# PLACA_CONECTORES.net
KiCad netlist of a schematic drawn in EAGLE
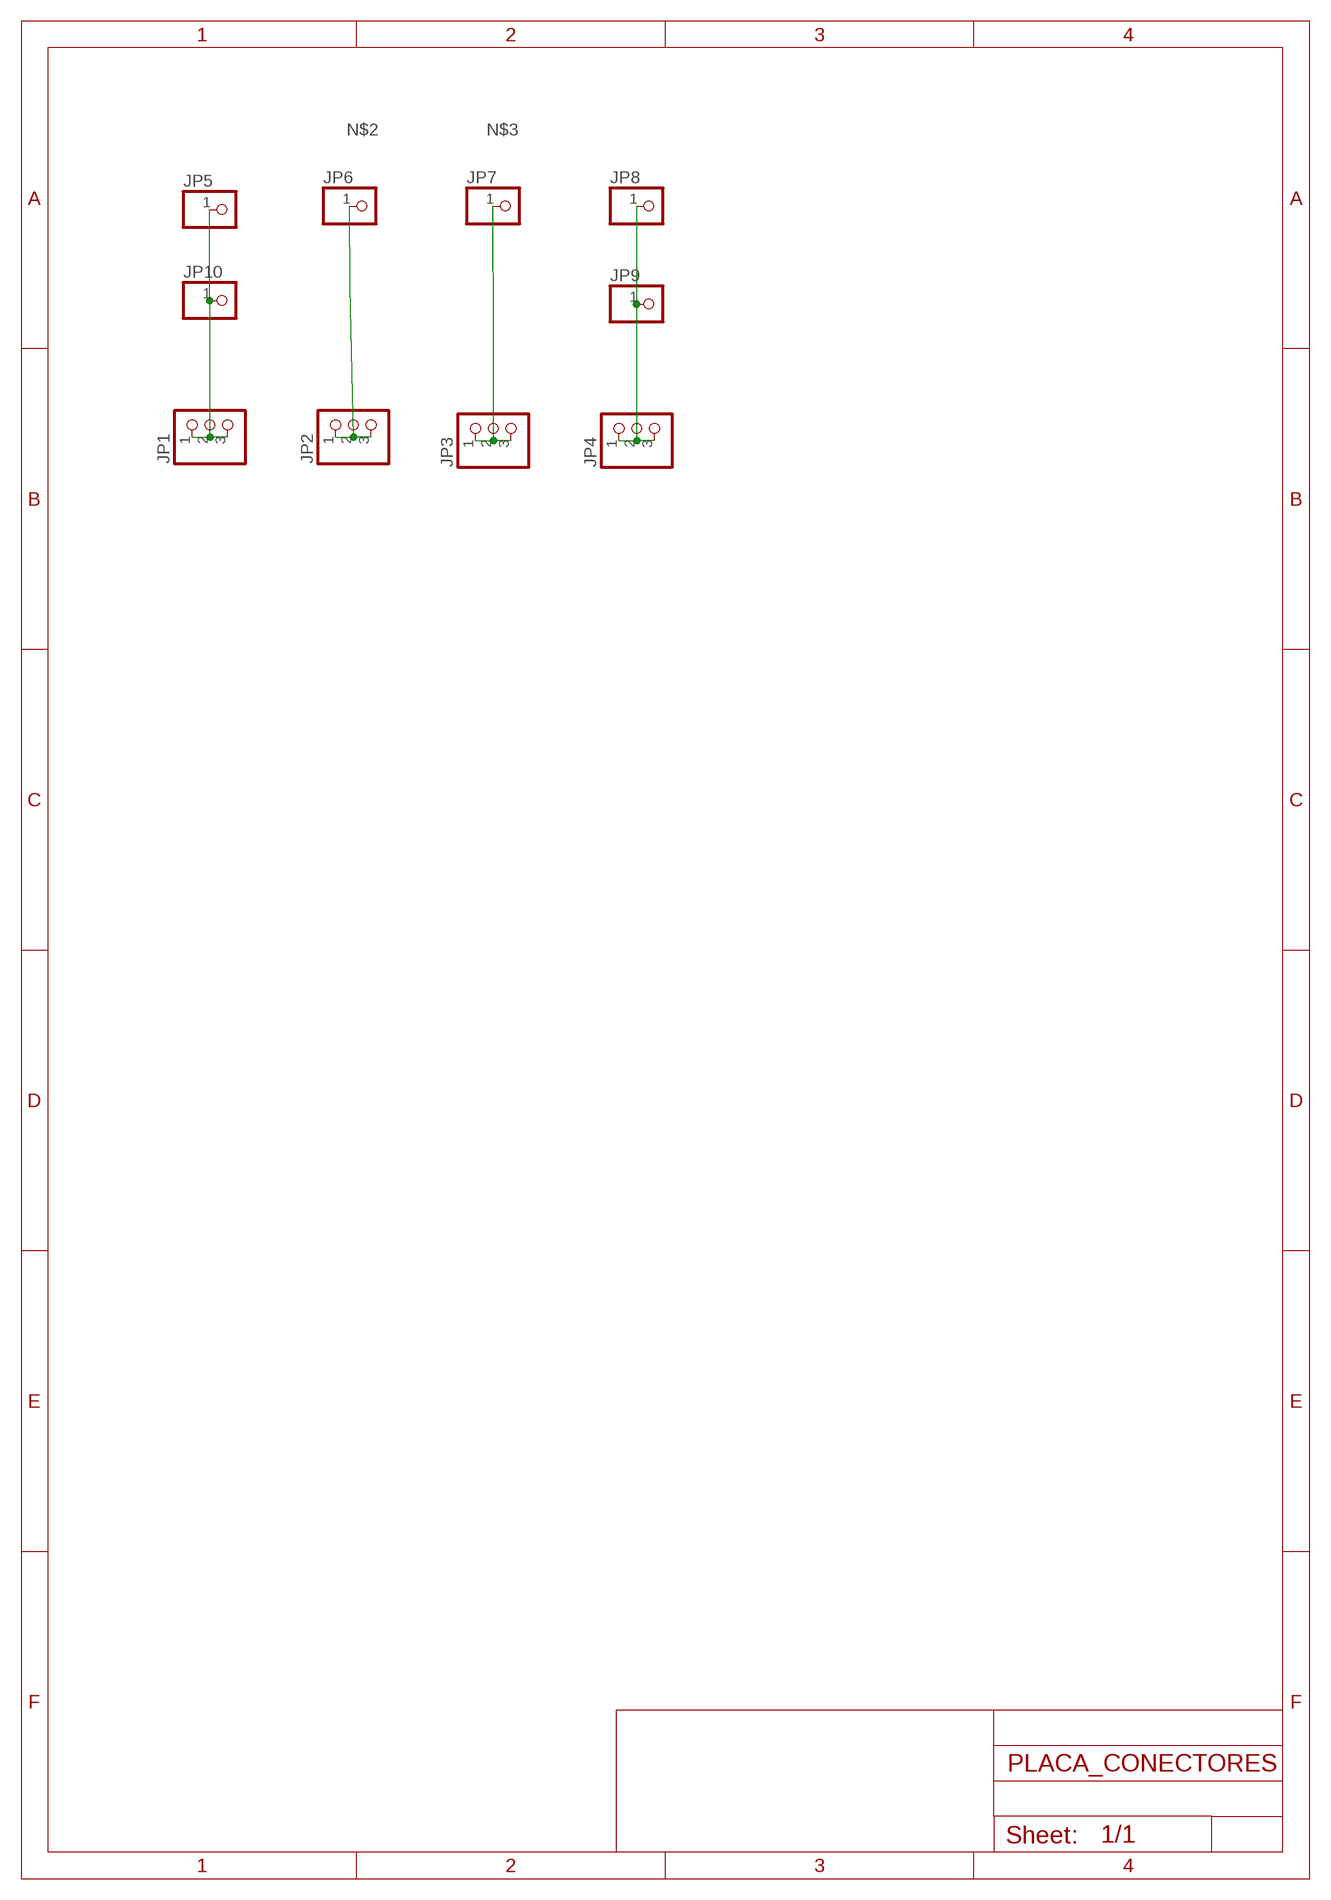
[diagram p0: schematic, sheet 1]

(export (version "E")
  (design (tool "Eeschema 10.0.6"))
  (components
    (comp (ref "JP1")
      (value "PINHD-1X3/90")
      (footprint "eagle-import:1X03_90")
      (libsource (lib "eagle-import") (part "PINHD-1X3/90"))
    )
    (comp (ref "JP2")
      (value "PINHD-1X3/90")
      (footprint "eagle-import:1X03_90")
      (libsource (lib "eagle-import") (part "PINHD-1X3/90"))
    )
    (comp (ref "JP3")
      (value "PINHD-1X3/90")
      (footprint "eagle-import:1X03_90")
      (libsource (lib "eagle-import") (part "PINHD-1X3/90"))
    )
    (comp (ref "JP4")
      (value "PINHD-1X3/90")
      (footprint "eagle-import:1X03_90")
      (libsource (lib "eagle-import") (part "PINHD-1X3/90"))
    )
    (comp (ref "JP5")
      (value "PINHD-1X1")
      (footprint "eagle-import:1X01")
      (libsource (lib "eagle-import") (part "PINHD-1X1"))
    )
    (comp (ref "JP6")
      (value "PINHD-1X1")
      (footprint "eagle-import:1X01")
      (libsource (lib "eagle-import") (part "PINHD-1X1"))
    )
    (comp (ref "JP7")
      (value "PINHD-1X1")
      (footprint "eagle-import:1X01")
      (libsource (lib "eagle-import") (part "PINHD-1X1"))
    )
    (comp (ref "JP8")
      (value "PINHD-1X1")
      (footprint "eagle-import:1X01")
      (libsource (lib "eagle-import") (part "PINHD-1X1"))
    )
    (comp (ref "JP9")
      (value "PINHD-1X1")
      (footprint "eagle-import:1X01")
      (libsource (lib "eagle-import") (part "PINHD-1X1"))
    )
    (comp (ref "JP10")
      (value "PINHD-1X1")
      (footprint "eagle-import:1X01")
      (libsource (lib "eagle-import") (part "PINHD-1X1"))
    )
  )
  (nets
    (net (code "1") (name "/N$2") (class "Default")
      (node (ref "JP2") (pin "1") (pinfunction "1_1") (pintype "passive"))
      (node (ref "JP2") (pin "2") (pinfunction "2_2") (pintype "passive"))
      (node (ref "JP2") (pin "3") (pinfunction "3_3") (pintype "passive"))
      (node (ref "JP6") (pin "1") (pinfunction "1_1") (pintype "passive"))
    )
    (net (code "2") (name "/N$3") (class "Default")
      (node (ref "JP3") (pin "1") (pinfunction "1_1") (pintype "passive"))
      (node (ref "JP3") (pin "2") (pinfunction "2_2") (pintype "passive"))
      (node (ref "JP3") (pin "3") (pinfunction "3_3") (pintype "passive"))
      (node (ref "JP7") (pin "1") (pinfunction "1_1") (pintype "passive"))
    )
    (net (code "3") (name "Net-(JP1-Pad1)") (class "Default")
      (node (ref "JP1") (pin "1") (pinfunction "1_1") (pintype "passive"))
      (node (ref "JP1") (pin "2") (pinfunction "2_2") (pintype "passive"))
      (node (ref "JP1") (pin "3") (pinfunction "3_3") (pintype "passive"))
      (node (ref "JP10") (pin "1") (pinfunction "1_1") (pintype "passive"))
      (node (ref "JP5") (pin "1") (pinfunction "1_1") (pintype "passive"))
    )
    (net (code "4") (name "Net-(JP4-Pad1)") (class "Default")
      (node (ref "JP4") (pin "1") (pinfunction "1_1") (pintype "passive"))
      (node (ref "JP4") (pin "2") (pinfunction "2_2") (pintype "passive"))
      (node (ref "JP4") (pin "3") (pinfunction "3_3") (pintype "passive"))
      (node (ref "JP8") (pin "1") (pinfunction "1_1") (pintype "passive"))
      (node (ref "JP9") (pin "1") (pinfunction "1_1") (pintype "passive"))
    )
  )
)
